# ProDoc__3_0_2025-09-29.net
KiCad netlist of a schematic drawn in EasyEDA Pro
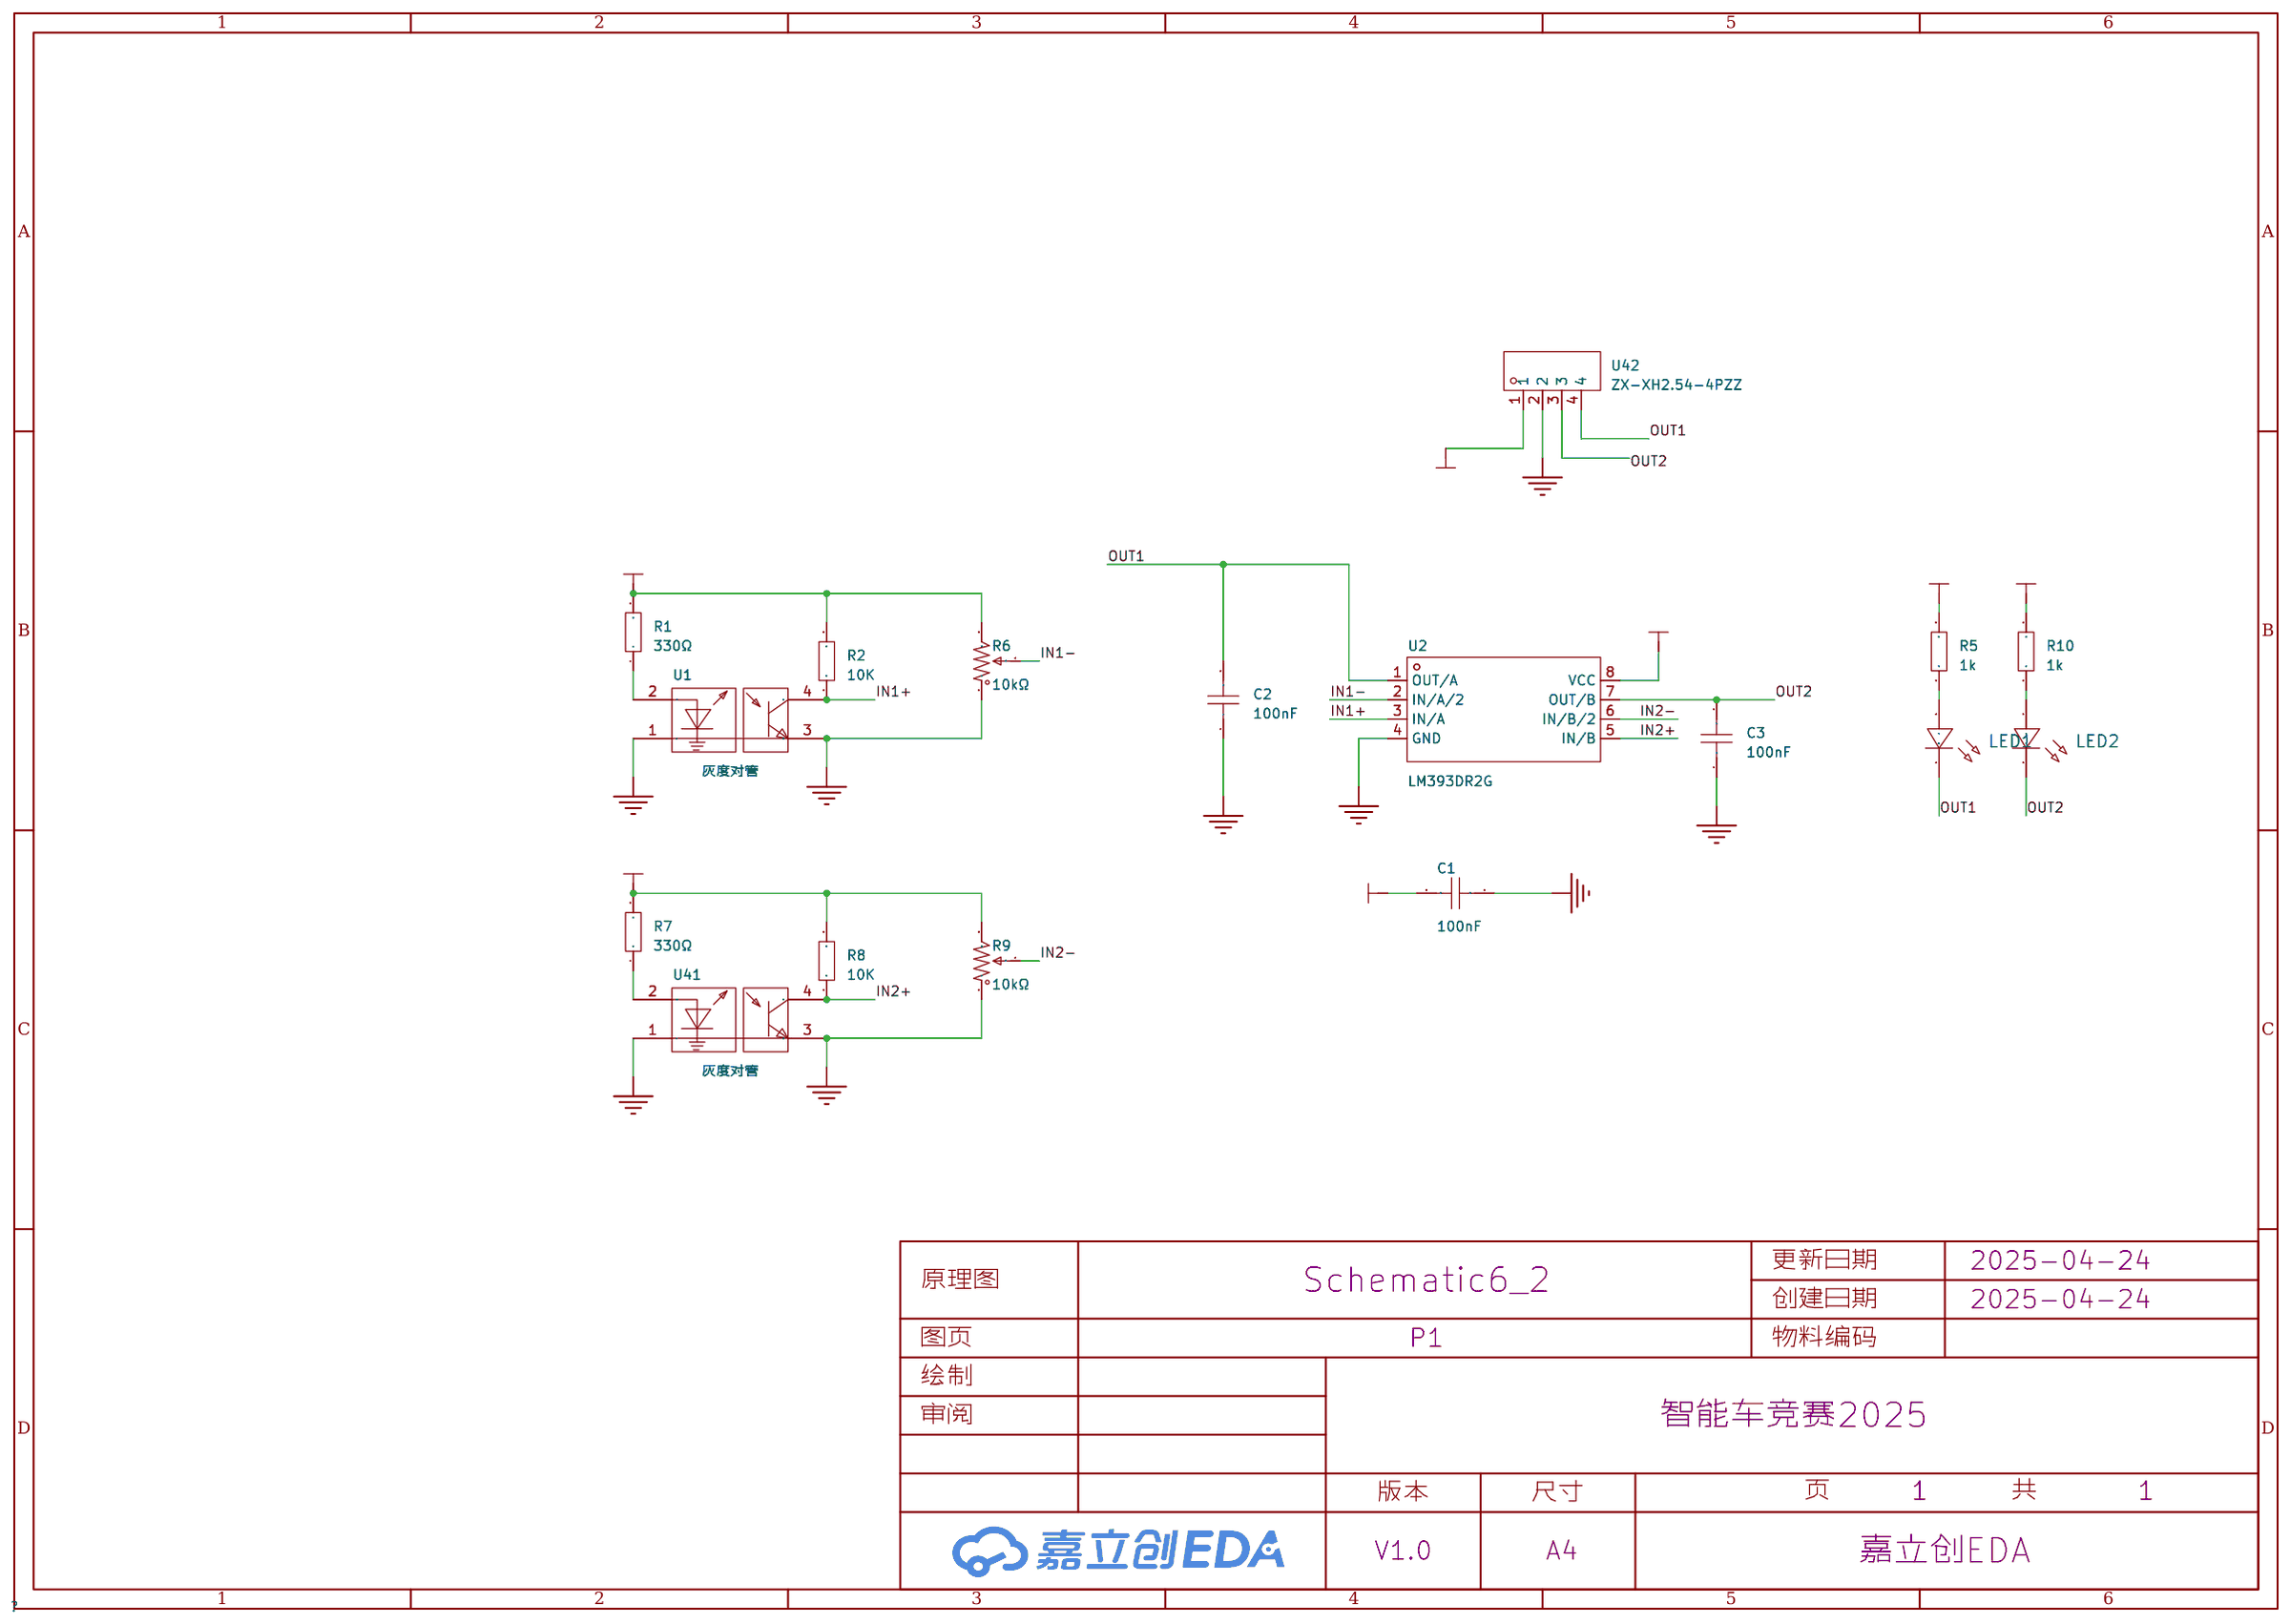
[diagram p0: schematic sheet]

(export (version "E")
  (design (tool "Eeschema 10.0.6"))
  (components
    (comp (ref "C1")
      (value "100nF")
      (footprint "easyedapro:C0603")
      (libsource (lib "easyedapro") (part "CapAcitance"))
    )
    (comp (ref "C2")
      (value "100nF")
      (footprint "easyedapro:C0603")
      (libsource (lib "easyedapro") (part "CapAcitance"))
    )
    (comp (ref "C3")
      (value "100nF")
      (footprint "easyedapro:C0603")
      (libsource (lib "easyedapro") (part "CapAcitance"))
    )
    (comp (ref "LED1")
      (value "~")
      (footprint "easyedapro:LED_0603")
      (libsource (lib "easyedapro") (part "LED_R"))
    )
    (comp (ref "LED2")
      (value "~")
      (footprint "easyedapro:LED_0603")
      (libsource (lib "easyedapro") (part "LED_R"))
    )
    (comp (ref "R1") (value "330Ω") (footprint "easyedapro:R0603") (libsource (lib "easyedapro") (part "电阻")))
    (comp (ref "R2") (value "10K") (footprint "easyedapro:R0603") (libsource (lib "easyedapro") (part "电阻")))
    (comp (ref "R5") (value "1k") (footprint "easyedapro:R0603") (libsource (lib "easyedapro") (part "电阻")))
    (comp (ref "R6")
      (value "10kΩ")
      (footprint "easyedapro:RES-ADJ-TH_3362P")
      (description "阻值:10kΩ;精度:±10%;")
      (fields (field (name "Manufacturer Part") "3362P-1-103") (field (name "Manufacturer") "BOCHEN(博晨)"))
      (libsource (lib "easyedapro") (part "3362P-1-103_C118956"))
    )
    (comp (ref "R7") (value "330Ω") (footprint "easyedapro:R0603") (libsource (lib "easyedapro") (part "电阻")))
    (comp (ref "R8") (value "10K") (footprint "easyedapro:R0603") (libsource (lib "easyedapro") (part "电阻")))
    (comp (ref "R9")
      (value "10kΩ")
      (footprint "easyedapro:RES-ADJ-TH_3362P")
      (description "阻值:10kΩ;精度:±10%;")
      (fields (field (name "Manufacturer Part") "3362P-1-103") (field (name "Manufacturer") "BOCHEN(博晨)"))
      (libsource (lib "easyedapro") (part "3362P-1-103_C118956"))
    )
    (comp (ref "R10") (value "1k") (footprint "easyedapro:R0603") (libsource (lib "easyedapro") (part "电阻")))
    (comp (ref "U1")
      (value "灰度对管")
      (footprint "easyedapro:OPTO-TH_ITR9909")
      (description "感应距离:-;集电极电流(最大值):50mA;")
      (fields (field (name "Manufacturer") "EVERLIGHT(亿光)"))
      (libsource (lib "easyedapro") (part "ITR9909"))
    )
    (comp (ref "U2")
      (value "LM393DR2G")
      (footprint "easyedapro:SOIC-8_L5.0-W4.0-P1.27-LS6.0-BL")
      (description "输入失调电压(Vos):5mV;输入偏置电流(Ib):250nA;")
      (fields (field (name "Manufacturer") "onsemi(安森美)"))
      (libsource (lib "easyedapro") (part "LM393DR2G"))
    )
    (comp (ref "U41")
      (value "灰度对管")
      (footprint "easyedapro:OPTO-TH_ITR9909")
      (description "感应距离:-;集电极电流(最大值):50mA;")
      (fields (field (name "Manufacturer") "EVERLIGHT(亿光)"))
      (libsource (lib "easyedapro") (part "ITR9909"))
    )
    (comp (ref "U42")
      (value "ZX-XH2.54-4PZZ")
      (footprint "easyedapro:CONN-TH_4P-P2.50_4PIN")
      (fields (field (name "Manufacturer") "Megastar(兆星)"))
      (libsource (lib "easyedapro") (part "ZX-XH2.54-4PZZ"))
    )
  )
  (nets
    (net (code "1") (name "/IN1+") (class "Default")
      (node (ref "R2") (pin "1") (pinfunction "1_1") (pintype "input"))
      (node (ref "U1") (pin "4") (pinfunction "4_4") (pintype "input"))
      (node (ref "U2") (pin "3") (pinfunction "IN/A_3") (pintype "unspecified"))
    )
    (net (code "2") (name "/IN1-") (class "Default")
      (node (ref "R6") (pin "2") (pinfunction "2_2") (pintype "unspecified"))
      (node (ref "U2") (pin "2") (pinfunction "IN/A/2_2") (pintype "unspecified"))
    )
    (net (code "3") (name "/IN2+") (class "Default")
      (node (ref "R8") (pin "1") (pinfunction "1_1") (pintype "input"))
      (node (ref "U2") (pin "5") (pinfunction "IN/B_5") (pintype "unspecified"))
      (node (ref "U41") (pin "4") (pinfunction "4_4") (pintype "input"))
    )
    (net (code "4") (name "/IN2-") (class "Default")
      (node (ref "R9") (pin "2") (pinfunction "2_2") (pintype "unspecified"))
      (node (ref "U2") (pin "6") (pinfunction "IN/B/2_6") (pintype "unspecified"))
    )
    (net (code "5") (name "/OUT1") (class "Default")
      (node (ref "C2") (pin "2") (pinfunction "2_2") (pintype "input"))
      (node (ref "LED1") (pin "1") (pinfunction "C_1") (pintype "input"))
      (node (ref "U2") (pin "1") (pinfunction "OUT/A_1") (pintype "unspecified"))
      (node (ref "U42") (pin "4") (pinfunction "4_4") (pintype "unspecified"))
    )
    (net (code "6") (name "/OUT2") (class "Default")
      (node (ref "C3") (pin "2") (pinfunction "2_2") (pintype "input"))
      (node (ref "LED2") (pin "1") (pinfunction "C_1") (pintype "input"))
      (node (ref "U2") (pin "7") (pinfunction "OUT/B_7") (pintype "unspecified"))
      (node (ref "U42") (pin "3") (pinfunction "3_3") (pintype "unspecified"))
    )
    (net (code "7") (name "GND") (class "Default")
      (node (ref "C1") (pin "1") (pinfunction "1_1") (pintype "input"))
      (node (ref "C2") (pin "1") (pinfunction "1_1") (pintype "input"))
      (node (ref "C3") (pin "1") (pinfunction "1_1") (pintype "input"))
      (node (ref "R6") (pin "1") (pinfunction "1_1") (pintype "unspecified"))
      (node (ref "R9") (pin "1") (pinfunction "1_1") (pintype "unspecified"))
      (node (ref "U1") (pin "1") (pinfunction "1_1") (pintype "input"))
      (node (ref "U1") (pin "3") (pinfunction "3_3") (pintype "input"))
      (node (ref "U2") (pin "4") (pinfunction "GND_4") (pintype "unspecified"))
      (node (ref "U41") (pin "1") (pinfunction "1_1") (pintype "input"))
      (node (ref "U41") (pin "3") (pinfunction "3_3") (pintype "input"))
      (node (ref "U42") (pin "2") (pinfunction "2_2") (pintype "unspecified"))
    )
    (net (code "8") (name "Net-(LED1-A)") (class "Default")
      (node (ref "LED1") (pin "2") (pinfunction "A_2") (pintype "input"))
      (node (ref "R5") (pin "1") (pinfunction "1_1") (pintype "input"))
    )
    (net (code "9") (name "Net-(LED2-A)") (class "Default")
      (node (ref "LED2") (pin "2") (pinfunction "A_2") (pintype "input"))
      (node (ref "R10") (pin "1") (pinfunction "1_1") (pintype "input"))
    )
    (net (code "10") (name "Net-(R1-Pad1)") (class "Default")
      (node (ref "R1") (pin "1") (pinfunction "1_1") (pintype "input"))
      (node (ref "U1") (pin "2") (pinfunction "2_2") (pintype "input"))
    )
    (net (code "11") (name "Net-(R7-Pad1)") (class "Default")
      (node (ref "R7") (pin "1") (pinfunction "1_1") (pintype "input"))
      (node (ref "U41") (pin "2") (pinfunction "2_2") (pintype "input"))
    )
    (net (code "12") (name "VCC") (class "Default")
      (node (ref "C1") (pin "2") (pinfunction "2_2") (pintype "input"))
      (node (ref "R1") (pin "2") (pinfunction "2_2") (pintype "input"))
      (node (ref "R10") (pin "2") (pinfunction "2_2") (pintype "input"))
      (node (ref "R2") (pin "2") (pinfunction "2_2") (pintype "input"))
      (node (ref "R5") (pin "2") (pinfunction "2_2") (pintype "input"))
      (node (ref "R6") (pin "3") (pinfunction "3_3") (pintype "unspecified"))
      (node (ref "R7") (pin "2") (pinfunction "2_2") (pintype "input"))
      (node (ref "R8") (pin "2") (pinfunction "2_2") (pintype "input"))
      (node (ref "R9") (pin "3") (pinfunction "3_3") (pintype "unspecified"))
      (node (ref "U2") (pin "8") (pinfunction "VCC_8") (pintype "unspecified"))
      (node (ref "U42") (pin "1") (pinfunction "1_1") (pintype "unspecified"))
    )
  )
)
